# MusicGloves.net
KiCad netlist of a schematic drawn in EAGLE
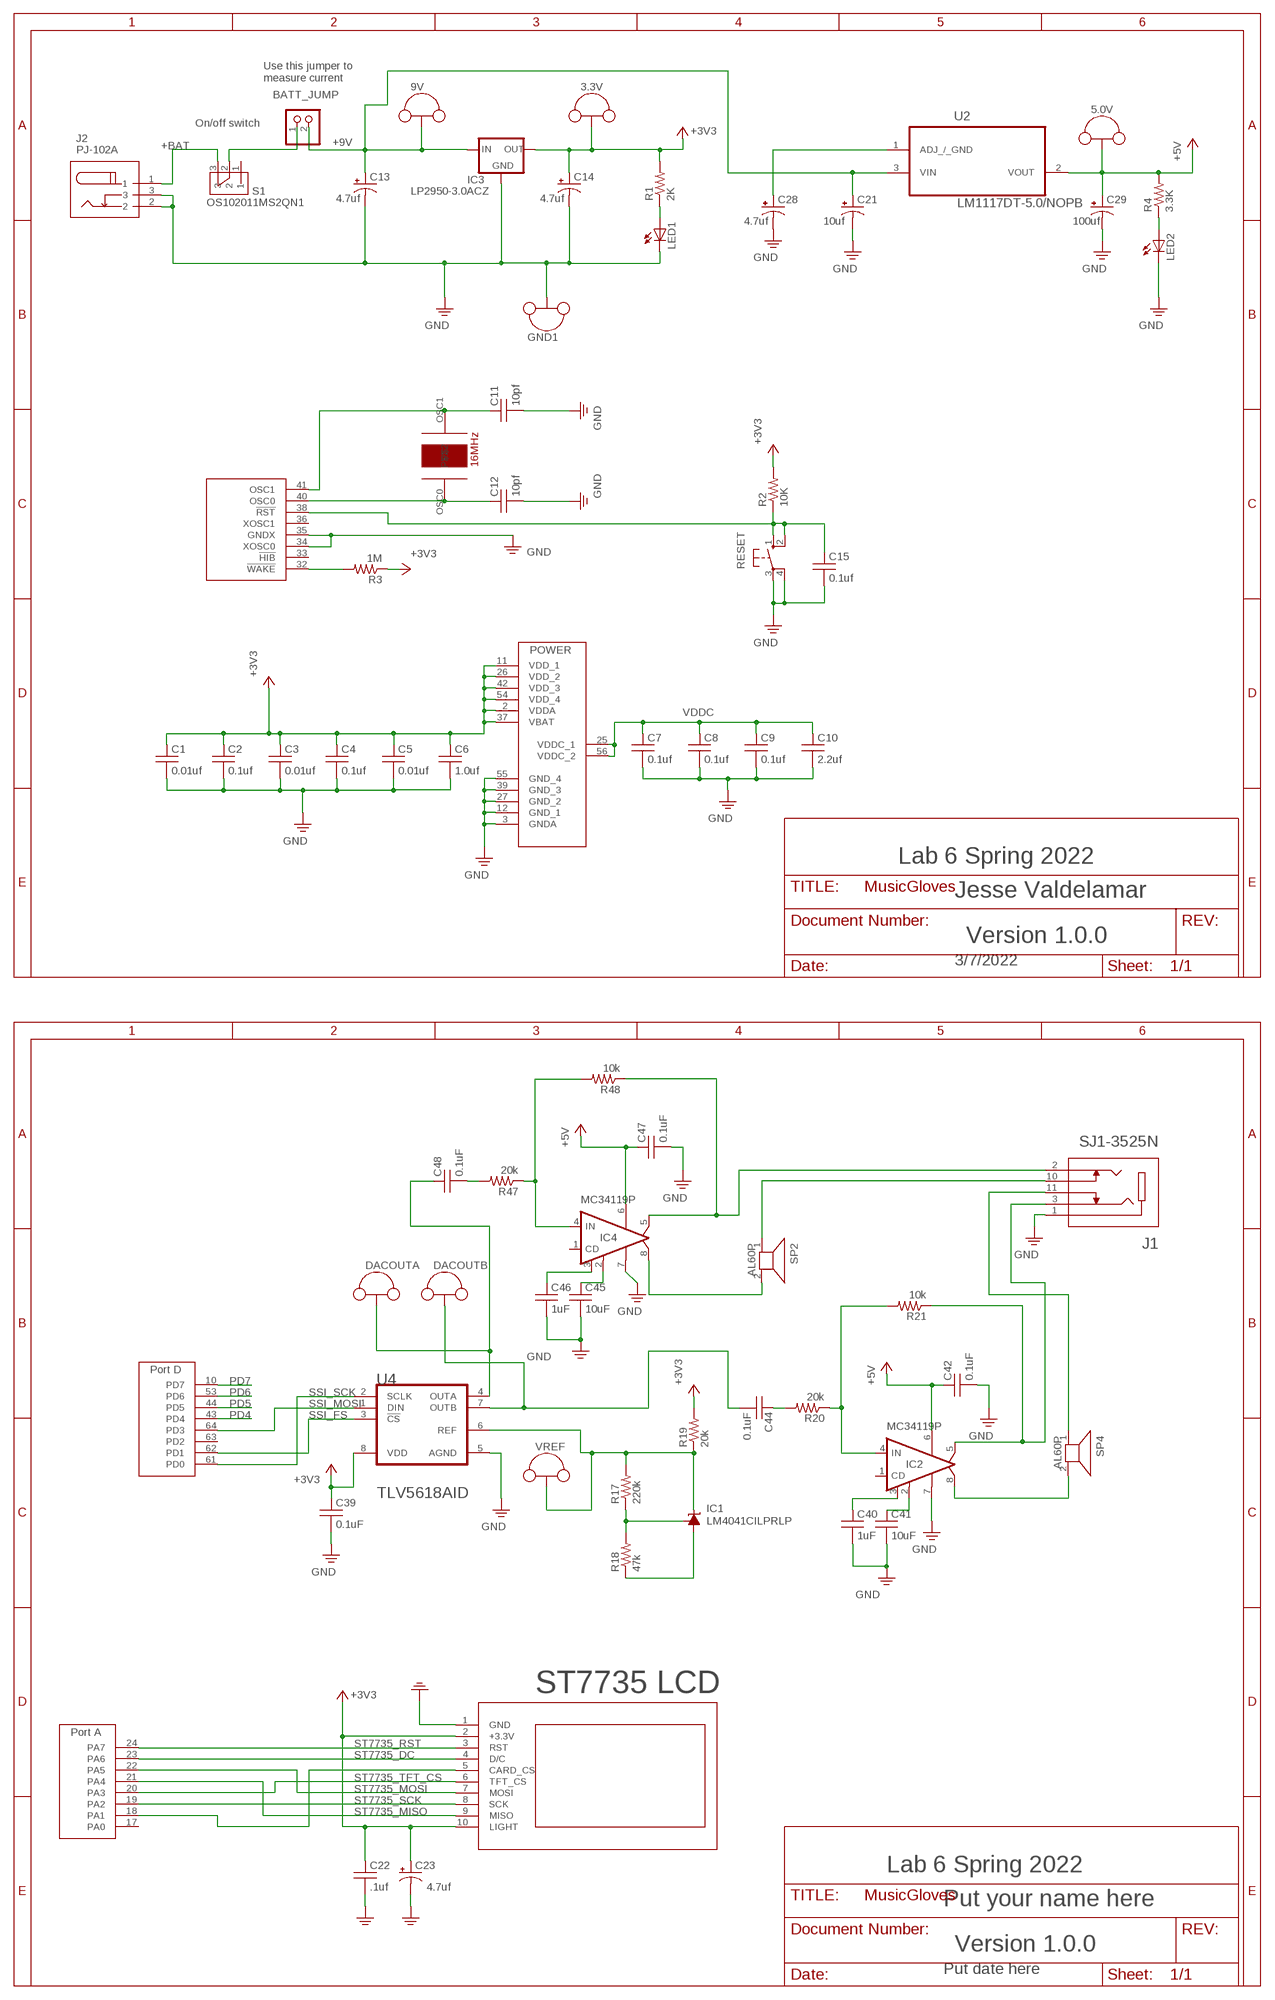
[diagram p0: schematic, sheet 1, part 1 of 2]
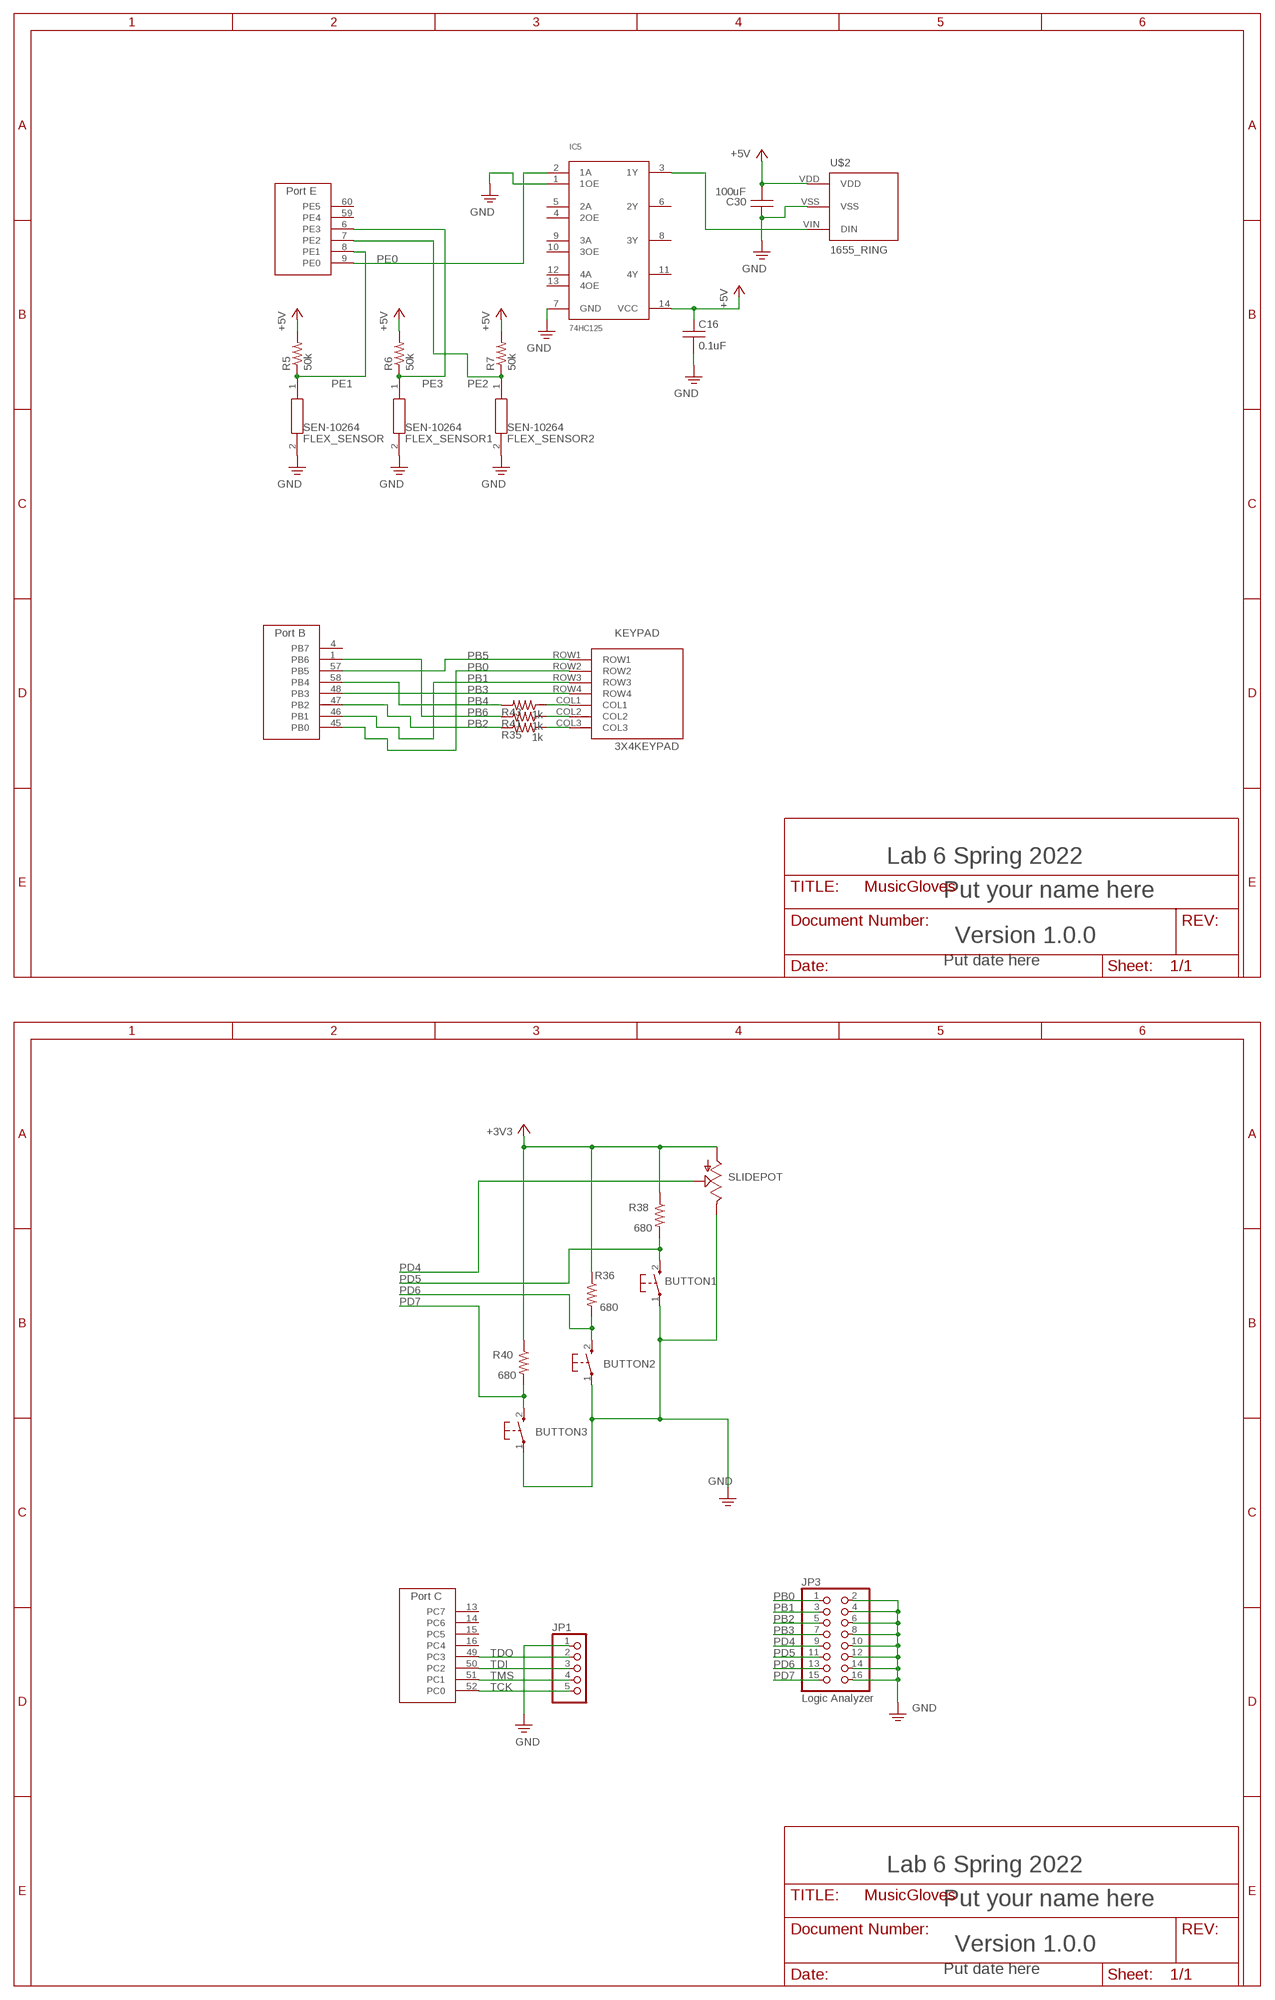
[diagram p1: schematic, sheet 1, part 2 of 2]

(export (version "E")
  (design (tool "Eeschema 10.0.6"))
  (components
    (comp (ref "3.3V")
      (value "TP_LOOP")
      (footprint "eagle-import:TP_LOOP")
      (libsource (lib "eagle-import") (part "TP_LOOP"))
    )
    (comp (ref "5.0V")
      (value "TP_LOOP")
      (footprint "eagle-import:TP_LOOP")
      (libsource (lib "eagle-import") (part "TP_LOOP"))
    )
    (comp (ref "9V")
      (value "TP_LOOP")
      (footprint "eagle-import:TP_LOOP")
      (libsource (lib "eagle-import") (part "TP_LOOP"))
    )
    (comp (ref "BATT_JUMP")
      (value "PINHD-1X2")
      (footprint "eagle-import:1X02")
      (libsource (lib "eagle-import") (part "PINHD-1X2"))
    )
    (comp (ref "BUTTON1")
      (value "B3F_1052_2HOLE")
      (footprint "eagle-import:B3F-10XX_2HOLE")
      (libsource (lib "eagle-import") (part "B3F_1052_2HOLE"))
    )
    (comp (ref "BUTTON2")
      (value "B3F_1052_2HOLE")
      (footprint "eagle-import:B3F-10XX_2HOLE")
      (libsource (lib "eagle-import") (part "B3F_1052_2HOLE"))
    )
    (comp (ref "BUTTON3")
      (value "B3F_1052_2HOLE")
      (footprint "eagle-import:B3F-10XX_2HOLE")
      (libsource (lib "eagle-import") (part "B3F_1052_2HOLE"))
    )
    (comp (ref "C1")
      (value "0.01uf")
      (footprint "eagle-import:CAP100MIL")
      (libsource (lib "eagle-import") (part "CAPACITOR025-024X044"))
    )
    (comp (ref "C2")
      (value "0.1uf")
      (footprint "eagle-import:CAP100MIL")
      (libsource (lib "eagle-import") (part "CAPACITOR025-024X044"))
    )
    (comp (ref "C3")
      (value "0.01uf")
      (footprint "eagle-import:CAP100MIL")
      (libsource (lib "eagle-import") (part "CAPACITOR025-024X044"))
    )
    (comp (ref "C4")
      (value "0.1uf")
      (footprint "eagle-import:CAP100MIL")
      (libsource (lib "eagle-import") (part "CAPACITOR025-024X044"))
    )
    (comp (ref "C5")
      (value "0.01uf")
      (footprint "eagle-import:CAP100MIL")
      (libsource (lib "eagle-import") (part "CAPACITOR025-024X044"))
    )
    (comp (ref "C6")
      (value "1.0uf")
      (footprint "eagle-import:CAP100MIL")
      (libsource (lib "eagle-import") (part "CAPACITOR025-024X044"))
    )
    (comp (ref "C7")
      (value "0.1uf")
      (footprint "eagle-import:CAP100MIL")
      (libsource (lib "eagle-import") (part "CAPACITOR025-024X044"))
    )
    (comp (ref "C8")
      (value "0.1uf")
      (footprint "eagle-import:CAP100MIL")
      (libsource (lib "eagle-import") (part "CAPACITOR025-024X044"))
    )
    (comp (ref "C9")
      (value "0.1uf")
      (footprint "eagle-import:CAP100MIL")
      (libsource (lib "eagle-import") (part "CAPACITOR025-024X044"))
    )
    (comp (ref "C10")
      (value "2.2uf")
      (footprint "eagle-import:CAP100MIL")
      (libsource (lib "eagle-import") (part "CAPACITOR025-024X044"))
    )
    (comp (ref "C11")
      (value "10pf")
      (footprint "eagle-import:CAP100MIL")
      (libsource (lib "eagle-import") (part "CAPACITOR025-024X044"))
    )
    (comp (ref "C12")
      (value "10pf")
      (footprint "eagle-import:CAP100MIL")
      (libsource (lib "eagle-import") (part "CAPACITOR025-024X044"))
    )
    (comp (ref "C13")
      (value "4.7uf")
      (footprint "eagle-import:CAP200MILPOLARIZED")
      (libsource (lib "eagle-import") (part "CAPACITOR_POLARIZEDE5-6"))
    )
    (comp (ref "C14")
      (value "4.7uf")
      (footprint "eagle-import:CAP200MILPOLARIZED")
      (libsource (lib "eagle-import") (part "CAPACITOR_POLARIZEDE5-6"))
    )
    (comp (ref "C15")
      (value "0.1uf")
      (footprint "eagle-import:CAP100MIL")
      (libsource (lib "eagle-import") (part "CAPACITOR025-024X044"))
    )
    (comp (ref "C16")
      (value "0.1uF")
      (footprint "eagle-import:CAP200MIL")
      (libsource (lib "eagle-import") (part "CAPACITOR050-024X044"))
    )
    (comp (ref "C21")
      (value "10uf")
      (footprint "eagle-import:CAP200MILPOLARIZED")
      (libsource (lib "eagle-import") (part "CAPACITOR_POLARIZEDE5-6"))
    )
    (comp (ref "C22")
      (value ".1uf")
      (footprint "eagle-import:CAP200MIL")
      (libsource (lib "eagle-import") (part "CAPACITOR050-024X044"))
    )
    (comp (ref "C23")
      (value "4.7uf")
      (footprint "eagle-import:CAP200MILPOLARIZED")
      (libsource (lib "eagle-import") (part "CAPACITOR_POLARIZEDE5-6"))
    )
    (comp (ref "C28")
      (value "4.7uf")
      (footprint "eagle-import:CAP200MILPOLARIZED")
      (libsource (lib "eagle-import") (part "CAPACITOR_POLARIZEDE5-6"))
    )
    (comp (ref "C29")
      (value "100uf")
      (footprint "eagle-import:CAP200MILPOLARIZED")
      (libsource (lib "eagle-import") (part "CAPACITOR_POLARIZEDE5-6"))
    )
    (comp (ref "C30")
      (value "100uF")
      (footprint "eagle-import:CAP200MIL")
      (libsource (lib "eagle-import") (part "CAPACITOR050-024X044"))
    )
    (comp (ref "C39")
      (value "0.1uF")
      (footprint "eagle-import:CAP200MIL")
      (libsource (lib "eagle-import") (part "CAPACITOR050-024X044"))
    )
    (comp (ref "C40")
      (value "1uF")
      (footprint "eagle-import:CAP200MIL")
      (libsource (lib "eagle-import") (part "CAPACITOR050-024X044"))
    )
    (comp (ref "C41")
      (value "10uF")
      (footprint "eagle-import:CAP200MIL")
      (libsource (lib "eagle-import") (part "CAPACITOR050-024X044"))
    )
    (comp (ref "C42")
      (value "0.1uF")
      (footprint "eagle-import:CAP200MIL")
      (libsource (lib "eagle-import") (part "CAPACITOR050-024X044"))
    )
    (comp (ref "C44")
      (value "0.1uF")
      (footprint "eagle-import:CAP200MIL")
      (libsource (lib "eagle-import") (part "CAPACITOR050-024X044"))
    )
    (comp (ref "C45")
      (value "10uF")
      (footprint "eagle-import:CAP200MIL")
      (libsource (lib "eagle-import") (part "CAPACITOR050-024X044"))
    )
    (comp (ref "C46")
      (value "1uF")
      (footprint "eagle-import:CAP200MIL")
      (libsource (lib "eagle-import") (part "CAPACITOR050-024X044"))
    )
    (comp (ref "C47")
      (value "0.1uF")
      (footprint "eagle-import:CAP200MIL")
      (libsource (lib "eagle-import") (part "CAPACITOR050-024X044"))
    )
    (comp (ref "C48")
      (value "0.1uF")
      (footprint "eagle-import:CAP200MIL")
      (libsource (lib "eagle-import") (part "CAPACITOR050-024X044"))
    )
    (comp (ref "DACOUTA")
      (value "TP_LOOP")
      (footprint "eagle-import:TP_LOOP")
      (libsource (lib "eagle-import") (part "TP_LOOP"))
    )
    (comp (ref "DACOUTB")
      (value "TP_LOOP")
      (footprint "eagle-import:TP_LOOP")
      (libsource (lib "eagle-import") (part "TP_LOOP"))
    )
    (comp (ref "FLEX_SENSOR")
      (value "SEN-10264")
      (footprint "eagle-import:RESAD2700W1900L700D500")
      (libsource (lib "eagle-import") (part "SEN-10264"))
    )
    (comp (ref "FLEX_SENSOR1")
      (value "SEN-10264")
      (footprint "eagle-import:RESAD2700W1900L700D500")
      (libsource (lib "eagle-import") (part "SEN-10264"))
    )
    (comp (ref "FLEX_SENSOR2")
      (value "SEN-10264")
      (footprint "eagle-import:RESAD2700W1900L700D500")
      (libsource (lib "eagle-import") (part "SEN-10264"))
    )
    (comp (ref "GND1")
      (value "TP_LOOP")
      (footprint "eagle-import:TP_LOOP")
      (libsource (lib "eagle-import") (part "TP_LOOP"))
    )
    (comp (ref "IC1")
      (value "LM4041CILPRLP")
      (footprint "eagle-import:LP_O-PBCY-W3")
      (fields
        (field (name "DIGI-KEY_PART_NUMBER") "296-22173-1-ND")
        (field (name "MF") "Texas Instruments")
        (field (name "MP") "LM4041CILPR")
      )
      (libsource (lib "eagle-import") (part "LM4041CILPRLP"))
    )
    (comp (ref "IC2")
      (value "MC34119P")
      (footprint "eagle-import:DIL08")
      (fields (field (name "MF") "NXP Semiconductors") (field (name "MP") "MC34119"))
      (libsource (lib "eagle-import") (part "MC34119P"))
    )
    (comp (ref "IC3")
      (value "LP2950-3.0ACZ")
      (footprint "eagle-import:TO92")
      (libsource (lib "eagle-import") (part "LP2950ACZ-3.0"))
    )
    (comp (ref "IC4")
      (value "MC34119P")
      (footprint "eagle-import:DIL08")
      (fields (field (name "MF") "NXP Semiconductors") (field (name "MP") "MC34119"))
      (libsource (lib "eagle-import") (part "MC34119P"))
    )
    (comp (ref "IC5")
      (value "74HC125")
      (footprint "eagle-import:SOIC-14")
      (fields (field (name "MF") "Nexperia USA"))
      (libsource (lib "eagle-import") (part "74HC125"))
    )
    (comp (ref "J1")
      (value "SJ1-3525N")
      (footprint "eagle-import:CUI_SJ1-3525N")
      (fields (field (name "MANUFACTURER") "CUI"))
      (libsource (lib "eagle-import") (part "SJ1-3525N"))
    )
    (comp (ref "J2")
      (value "PJ-102A")
      (footprint "eagle-import:PJ-102AH")
      (fields (field (name "MOUSER_PART_NUMBER") "490-PJ-102A"))
      (libsource (lib "eagle-import") (part "PJ-102A"))
    )
    (comp (ref "JP1")
      (value "PINHD-1X5")
      (footprint "eagle-import:1X05")
      (libsource (lib "eagle-import") (part "PINHD-1X5"))
    )
    (comp (ref "JP3")
      (value "Logic Analyzer")
      (footprint "eagle-import:2X08")
      (libsource (lib "eagle-import") (part "PINHD-2X8"))
    )
    (comp (ref "KEYPAD")
      (value "3X4KEYPAD")
      (footprint "eagle-import:3X4KEYPAD")
      (libsource (lib "eagle-import") (part "3X4KEYPAD"))
    )
    (comp (ref "LED1")
      (value "LED3MM")
      (footprint "eagle-import:LED3MM")
      (libsource (lib "eagle-import") (part "LED3MM"))
    )
    (comp (ref "LED2")
      (value "LED3MM")
      (footprint "eagle-import:LED3MM")
      (libsource (lib "eagle-import") (part "LED3MM"))
    )
    (comp (ref "R1")
      (value "2K")
      (footprint "eagle-import:RES200MIL")
      (libsource (lib "eagle-import") (part "RESISTOR0204/5"))
    )
    (comp (ref "R2")
      (value "10K")
      (footprint "eagle-import:RES200MIL")
      (libsource (lib "eagle-import") (part "RESISTOR0204/5"))
    )
    (comp (ref "R3")
      (value "1M")
      (footprint "eagle-import:RES200MIL")
      (libsource (lib "eagle-import") (part "RESISTOR0204/5"))
    )
    (comp (ref "R4")
      (value "3.3K")
      (footprint "eagle-import:RES200MIL")
      (libsource (lib "eagle-import") (part "RESISTOR0204/5"))
    )
    (comp (ref "R5")
      (value "50k")
      (footprint "eagle-import:RES200MIL")
      (libsource (lib "eagle-import") (part "RESISTOR0204/5"))
    )
    (comp (ref "R6")
      (value "50k")
      (footprint "eagle-import:RES200MIL")
      (libsource (lib "eagle-import") (part "RESISTOR0204/5"))
    )
    (comp (ref "R7")
      (value "50k")
      (footprint "eagle-import:RES200MIL")
      (libsource (lib "eagle-import") (part "RESISTOR0204/5"))
    )
    (comp (ref "R17")
      (value "220k")
      (footprint "eagle-import:RES200MIL")
      (libsource (lib "eagle-import") (part "RESISTOR0204/5"))
    )
    (comp (ref "R18")
      (value "47k")
      (footprint "eagle-import:RES200MIL")
      (libsource (lib "eagle-import") (part "RESISTOR0204/5"))
    )
    (comp (ref "R19")
      (value "20k")
      (footprint "eagle-import:RES200MIL")
      (libsource (lib "eagle-import") (part "RESISTOR0204/5"))
    )
    (comp (ref "R20")
      (value "20k")
      (footprint "eagle-import:RES200MIL")
      (libsource (lib "eagle-import") (part "RESISTOR0204/5"))
    )
    (comp (ref "R21")
      (value "10k")
      (footprint "eagle-import:RES200MIL")
      (libsource (lib "eagle-import") (part "RESISTOR0204/5"))
    )
    (comp (ref "R35")
      (value "1k")
      (footprint "eagle-import:0204_5")
      (libsource (lib "eagle-import") (part "R-US_0204/5"))
    )
    (comp (ref "R36")
      (value "680")
      (footprint "eagle-import:0204_5")
      (libsource (lib "eagle-import") (part "R-US_0204/5"))
    )
    (comp (ref "R38")
      (value "680")
      (footprint "eagle-import:0204_5")
      (libsource (lib "eagle-import") (part "R-US_0204/5"))
    )
    (comp (ref "R40")
      (value "680")
      (footprint "eagle-import:0204_5")
      (libsource (lib "eagle-import") (part "R-US_0204/5"))
    )
    (comp (ref "R41")
      (value "1k")
      (footprint "eagle-import:0204_5")
      (libsource (lib "eagle-import") (part "R-US_0204/5"))
    )
    (comp (ref "R43")
      (value "1k")
      (footprint "eagle-import:0204_5")
      (libsource (lib "eagle-import") (part "R-US_0204/5"))
    )
    (comp (ref "R47")
      (value "20k")
      (footprint "eagle-import:RES200MIL")
      (libsource (lib "eagle-import") (part "RESISTOR0204/5"))
    )
    (comp (ref "R48")
      (value "10k")
      (footprint "eagle-import:RES200MIL")
      (libsource (lib "eagle-import") (part "RESISTOR0204/5"))
    )
    (comp (ref "RESET")
      (value "B3F-1052")
      (footprint "eagle-import:B3F-10XX")
      (fields (field (name "MPN") "B3F-1000"))
      (libsource (lib "eagle-import") (part "B3F-1052"))
    )
    (comp (ref "S1")
      (value "OS102011MS2QN1")
      (footprint "eagle-import:SW_OS102011MS2QN1")
      (fields (field (name "MF") "C&K"))
      (libsource (lib "eagle-import") (part "OS102011MS2QN1"))
    )
    (comp (ref "SLIDEPOT")
      (value "POTENTIOMETER_PTA2043B25U")
      (footprint "eagle-import:PTA2043")
      (libsource (lib "eagle-import") (part "POTENTIOMETER_PTA2043B25U"))
    )
    (comp (ref "SP2")
      (value "AL60P")
      (footprint "eagle-import:AL60P")
      (libsource (lib "eagle-import") (part "AL60P"))
    )
    (comp (ref "SP4")
      (value "AL60P")
      (footprint "eagle-import:AL60P")
      (libsource (lib "eagle-import") (part "AL60P"))
    )
    (comp (ref "U$2")
      (value "1655_RING")
      (footprint "eagle-import:LED_1655_RING")
      (libsource (lib "eagle-import") (part "1655_RING"))
    )
    (comp (ref "U$3")
      (value "ST7735")
      (footprint "eagle-import:ST7735")
      (libsource (lib "eagle-import") (part "ST7735"))
    )
    (comp (ref "U1")
      (value "TM4C123GH6PM")
      (footprint "eagle-import:QFP50P1200X1200X160-64N")
      (libsource (lib "eagle-import") (part "TM4C123GH6PM"))
    )
    (comp (ref "U2")
      (value "LM1117DT-5.0/NOPB")
      (footprint "eagle-import:TO228P970X238-3N")
      (fields (field (name "MF") "Texas Instruments"))
      (libsource (lib "eagle-import") (part "LM1117DT-5.0/NOPB"))
    )
    (comp (ref "U4")
      (value "TEXAS_INSTRUMENTS_TLV5618AIDTEXAS_INSTRUMENTS_TLV5618AID_0_0")
      (footprint "eagle-import:TEXAS_INSTRUMENTS_TLV5618AID_0")
      (fields (field (name "MF") "Texas Instruments") (field (name "MPN") "TLV5618AID"))
      (libsource (lib "eagle-import") (part "TEXAS_INSTRUMENTS_TLV5618AIDTEXAS_INSTRUMENTS_TLV5618AID_0_0"))
    )
    (comp (ref "VREF")
      (value "TP_LOOP")
      (footprint "eagle-import:TP_LOOP")
      (libsource (lib "eagle-import") (part "TP_LOOP"))
    )
    (comp (ref "Y1")
      (value "16MHZ_CRYSTAL")
      (footprint "eagle-import:16MHZ_CRYSTAL")
      (libsource (lib "eagle-import") (part "16MHZ_CRYSTAL"))
    )
  )
  (nets
    (net (code "1") (name "+3V3") (class "Default")
      (node (ref "3.3V") (pin "P$1") (pinfunction "TP_P$1") (pintype "bidirectional"))
      (node (ref "3.3V") (pin "P$2") (pinfunction "TP_P$2") (pintype "bidirectional"))
      (node (ref "C1") (pin "1") (pinfunction "1_1") (pintype "passive"))
      (node (ref "C14") (pin "+") (pinfunction "+_+") (pintype "passive"))
      (node (ref "C2") (pin "1") (pinfunction "1_1") (pintype "passive"))
      (node (ref "C22") (pin "1") (pinfunction "1_1") (pintype "passive"))
      (node (ref "C23") (pin "+") (pinfunction "+_+") (pintype "passive"))
      (node (ref "C3") (pin "1") (pinfunction "1_1") (pintype "passive"))
      (node (ref "C39") (pin "1") (pinfunction "1_1") (pintype "passive"))
      (node (ref "C4") (pin "1") (pinfunction "1_1") (pintype "passive"))
      (node (ref "C5") (pin "1") (pinfunction "1_1") (pintype "passive"))
      (node (ref "C6") (pin "1") (pinfunction "1_1") (pintype "passive"))
      (node (ref "IC3") (pin "1") (pinfunction "OUT_1") (pintype "passive"))
      (node (ref "R1") (pin "2") (pinfunction "2_2") (pintype "passive"))
      (node (ref "R19") (pin "2") (pinfunction "2_2") (pintype "passive"))
      (node (ref "R2") (pin "2") (pinfunction "2_2") (pintype "passive"))
      (node (ref "R3") (pin "1") (pinfunction "1_1") (pintype "passive"))
      (node (ref "R36") (pin "1") (pinfunction "1_1") (pintype "passive"))
      (node (ref "R38") (pin "1") (pinfunction "1_1") (pintype "passive"))
      (node (ref "R40") (pin "1") (pinfunction "1_1") (pintype "passive"))
      (node (ref "SLIDEPOT") (pin "3") (pinfunction "A_3") (pintype "passive"))
      (node (ref "U$3") (pin "10") (pinfunction "LIGHT_10") (pintype "bidirectional"))
      (node (ref "U$3") (pin "2") (pinfunction "+3.3V_2") (pintype "bidirectional"))
      (node (ref "U1") (pin "11") (pinfunction "VDD_1_11") (pintype "bidirectional"))
      (node (ref "U1") (pin "2") (pinfunction "VDDA_2") (pintype "bidirectional"))
      (node (ref "U1") (pin "26") (pinfunction "VDD_2_26") (pintype "bidirectional"))
      (node (ref "U1") (pin "37") (pinfunction "VBAT_37") (pintype "bidirectional"))
      (node (ref "U1") (pin "42") (pinfunction "VDD_3_42") (pintype "bidirectional"))
      (node (ref "U1") (pin "54") (pinfunction "VDD_4_54") (pintype "bidirectional"))
      (node (ref "U4") (pin "8") (pinfunction "VDD_8") (pintype "power_in"))
    )
    (net (code "2") (name "+5V") (class "Default")
      (node (ref "5.0V") (pin "P$1") (pinfunction "TP_P$1") (pintype "bidirectional"))
      (node (ref "5.0V") (pin "P$2") (pinfunction "TP_P$2") (pintype "bidirectional"))
      (node (ref "C16") (pin "1") (pinfunction "1_1") (pintype "passive"))
      (node (ref "C29") (pin "+") (pinfunction "+_+") (pintype "passive"))
      (node (ref "C30") (pin "2") (pinfunction "2_2") (pintype "passive"))
      (node (ref "C42") (pin "1") (pinfunction "1_1") (pintype "passive"))
      (node (ref "C47") (pin "1") (pinfunction "1_1") (pintype "passive"))
      (node (ref "IC2") (pin "6") (pinfunction "VCC_6") (pintype "power_in"))
      (node (ref "IC4") (pin "6") (pinfunction "VCC_6") (pintype "power_in"))
      (node (ref "IC5") (pin "14") (pinfunction "VCC_14") (pintype "bidirectional"))
      (node (ref "R4") (pin "2") (pinfunction "2_2") (pintype "passive"))
      (node (ref "R5") (pin "2") (pinfunction "2_2") (pintype "passive"))
      (node (ref "R6") (pin "2") (pinfunction "2_2") (pintype "passive"))
      (node (ref "R7") (pin "2") (pinfunction "2_2") (pintype "passive"))
      (node (ref "U$2") (pin "VDD") (pinfunction "VDD_VDD") (pintype "power_in"))
      (node (ref "U2") (pin "2") (pinfunction "VOUT_2") (pintype "output"))
    )
    (net (code "3") (name "/+9V") (class "Default")
      (node (ref "9V") (pin "P$1") (pinfunction "TP_P$1") (pintype "bidirectional"))
      (node (ref "9V") (pin "P$2") (pinfunction "TP_P$2") (pintype "bidirectional"))
      (node (ref "BATT_JUMP") (pin "2") (pinfunction "2_2") (pintype "passive"))
      (node (ref "C13") (pin "+") (pinfunction "+_+") (pintype "passive"))
      (node (ref "C21") (pin "+") (pinfunction "+_+") (pintype "passive"))
      (node (ref "IC3") (pin "3") (pinfunction "IN_3") (pintype "input"))
      (node (ref "U2") (pin "3") (pinfunction "VIN_3") (pintype "input"))
    )
    (net (code "4") (name "/+BAT") (class "Default")
      (node (ref "J2") (pin "1") (pinfunction "1_1") (pintype "bidirectional"))
      (node (ref "S1") (pin "3") (pinfunction "3_3") (pintype "passive"))
    )
    (net (code "5") (name "/PB0") (class "Default")
      (node (ref "JP3") (pin "1") (pinfunction "1_1") (pintype "passive"))
      (node (ref "KEYPAD") (pin "ROW2") (pinfunction "ROW2_ROW2") (pintype "bidirectional"))
      (node (ref "U1") (pin "45") (pinfunction "PB0_45") (pintype "bidirectional"))
    )
    (net (code "6") (name "/PB1") (class "Default")
      (node (ref "JP3") (pin "3") (pinfunction "3_3") (pintype "passive"))
      (node (ref "KEYPAD") (pin "ROW3") (pinfunction "ROW3_ROW3") (pintype "bidirectional"))
      (node (ref "U1") (pin "46") (pinfunction "PB1_46") (pintype "bidirectional"))
    )
    (net (code "7") (name "/PB2") (class "Default")
      (node (ref "JP3") (pin "5") (pinfunction "5_5") (pintype "passive"))
      (node (ref "R35") (pin "2") (pinfunction "2_2") (pintype "passive"))
      (node (ref "U1") (pin "47") (pinfunction "PB2_47") (pintype "bidirectional"))
    )
    (net (code "8") (name "/PB3") (class "Default")
      (node (ref "JP3") (pin "7") (pinfunction "7_7") (pintype "passive"))
      (node (ref "KEYPAD") (pin "ROW4") (pinfunction "ROW4_ROW4") (pintype "bidirectional"))
      (node (ref "U1") (pin "48") (pinfunction "PB3_48") (pintype "bidirectional"))
    )
    (net (code "9") (name "/PB4") (class "Default")
      (node (ref "R43") (pin "2") (pinfunction "2_2") (pintype "passive"))
      (node (ref "U1") (pin "58") (pinfunction "PB4_58") (pintype "bidirectional"))
    )
    (net (code "10") (name "/PB5") (class "Default")
      (node (ref "KEYPAD") (pin "ROW1") (pinfunction "ROW1_ROW1") (pintype "bidirectional"))
      (node (ref "U1") (pin "57") (pinfunction "PB5_57") (pintype "bidirectional"))
    )
    (net (code "11") (name "/PB6") (class "Default")
      (node (ref "R41") (pin "2") (pinfunction "2_2") (pintype "passive"))
      (node (ref "U1") (pin "1") (pinfunction "PB6_1") (pintype "bidirectional"))
    )
    (net (code "12") (name "/PD4") (class "Default")
      (node (ref "JP3") (pin "9") (pinfunction "9_9") (pintype "passive"))
      (node (ref "SLIDEPOT") (pin "2") (pinfunction "S_2") (pintype "passive"))
      (node (ref "U1") (pin "43") (pinfunction "PD4_43") (pintype "bidirectional"))
    )
    (net (code "13") (name "/PD5") (class "Default")
      (node (ref "BUTTON1") (pin "2") (pinfunction "S_2") (pintype "passive"))
      (node (ref "JP3") (pin "11") (pinfunction "11_11") (pintype "passive"))
      (node (ref "R38") (pin "2") (pinfunction "2_2") (pintype "passive"))
      (node (ref "U1") (pin "44") (pinfunction "PD5_44") (pintype "bidirectional"))
    )
    (net (code "14") (name "/PD6") (class "Default")
      (node (ref "BUTTON2") (pin "2") (pinfunction "S_2") (pintype "passive"))
      (node (ref "JP3") (pin "13") (pinfunction "13_13") (pintype "passive"))
      (node (ref "R36") (pin "2") (pinfunction "2_2") (pintype "passive"))
      (node (ref "U1") (pin "53") (pinfunction "PD6_53") (pintype "bidirectional"))
    )
    (net (code "15") (name "/PD7") (class "Default")
      (node (ref "BUTTON3") (pin "2") (pinfunction "S_2") (pintype "passive"))
      (node (ref "JP3") (pin "15") (pinfunction "15_15") (pintype "passive"))
      (node (ref "R40") (pin "2") (pinfunction "2_2") (pintype "passive"))
      (node (ref "U1") (pin "10") (pinfunction "PD7_10") (pintype "bidirectional"))
    )
    (net (code "16") (name "/PE0") (class "Default")
      (node (ref "IC5") (pin "2") (pinfunction "1A_2") (pintype "bidirectional"))
      (node (ref "U1") (pin "9") (pinfunction "PE0_9") (pintype "bidirectional"))
    )
    (net (code "17") (name "/PE1") (class "Default")
      (node (ref "FLEX_SENSOR") (pin "1") (pinfunction "1_1") (pintype "bidirectional"))
      (node (ref "R5") (pin "1") (pinfunction "1_1") (pintype "passive"))
      (node (ref "U1") (pin "8") (pinfunction "PE1_8") (pintype "bidirectional"))
    )
    (net (code "18") (name "/PE2") (class "Default")
      (node (ref "FLEX_SENSOR2") (pin "1") (pinfunction "1_1") (pintype "bidirectional"))
      (node (ref "R7") (pin "1") (pinfunction "1_1") (pintype "passive"))
      (node (ref "U1") (pin "7") (pinfunction "PE2_7") (pintype "bidirectional"))
    )
    (net (code "19") (name "/PE3") (class "Default")
      (node (ref "FLEX_SENSOR1") (pin "1") (pinfunction "1_1") (pintype "bidirectional"))
      (node (ref "R6") (pin "1") (pinfunction "1_1") (pintype "passive"))
      (node (ref "U1") (pin "6") (pinfunction "PE3_6") (pintype "bidirectional"))
    )
    (net (code "20") (name "/SSI_FS") (class "Default")
      (node (ref "U1") (pin "62") (pinfunction "PD1_62") (pintype "bidirectional"))
      (node (ref "U4") (pin "3") (pinfunction "~{CS}_3") (pintype "input"))
    )
    (net (code "21") (name "/SSI_MOSI") (class "Default")
      (node (ref "U1") (pin "64") (pinfunction "PD3_64") (pintype "bidirectional"))
      (node (ref "U4") (pin "1") (pinfunction "DIN_1") (pintype "input"))
    )
    (net (code "22") (name "/SSI_SCK") (class "Default")
      (node (ref "U1") (pin "61") (pinfunction "PD0_61") (pintype "bidirectional"))
      (node (ref "U4") (pin "2") (pinfunction "SCLK_2") (pintype "input"))
    )
    (net (code "23") (name "/ST7735_DC") (class "Default")
      (node (ref "U$3") (pin "4") (pinfunction "D/C_4") (pintype "bidirectional"))
      (node (ref "U1") (pin "23") (pinfunction "PA6_23") (pintype "bidirectional"))
    )
    (net (code "24") (name "/ST7735_MISO") (class "Default")
      (node (ref "U$3") (pin "9") (pinfunction "MISO_9") (pintype "bidirectional"))
      (node (ref "U1") (pin "21") (pinfunction "PA4_21") (pintype "bidirectional"))
    )
    (net (code "25") (name "/ST7735_MOSI") (class "Default")
      (node (ref "U$3") (pin "7") (pinfunction "MOSI_7") (pintype "bidirectional"))
      (node (ref "U1") (pin "22") (pinfunction "PA5_22") (pintype "bidirectional"))
    )
    (net (code "26") (name "/ST7735_RST") (class "Default")
      (node (ref "U$3") (pin "3") (pinfunction "RST_3") (pintype "bidirectional"))
      (node (ref "U1") (pin "24") (pinfunction "PA7_24") (pintype "bidirectional"))
    )
    (net (code "27") (name "/ST7735_SCK") (class "Default")
      (node (ref "U$3") (pin "8") (pinfunction "SCK_8") (pintype "bidirectional"))
      (node (ref "U1") (pin "19") (pinfunction "PA2_19") (pintype "bidirectional"))
    )
    (net (code "28") (name "/ST7735_TFT_CS") (class "Default")
      (node (ref "U$3") (pin "6") (pinfunction "TFT_CS_6") (pintype "bidirectional"))
      (node (ref "U1") (pin "20") (pinfunction "PA3_20") (pintype "bidirectional"))
    )
    (net (code "29") (name "/TCK") (class "Default")
      (node (ref "JP1") (pin "5") (pinfunction "5_5") (pintype "passive"))
      (node (ref "U1") (pin "52") (pinfunction "PC0_52") (pintype "bidirectional"))
    )
    (net (code "30") (name "/TDI") (class "Default")
      (node (ref "JP1") (pin "3") (pinfunction "3_3") (pintype "passive"))
      (node (ref "U1") (pin "50") (pinfunction "PC2_50") (pintype "bidirectional"))
    )
    (net (code "31") (name "/TDO") (class "Default")
      (node (ref "JP1") (pin "2") (pinfunction "2_2") (pintype "passive"))
      (node (ref "U1") (pin "49") (pinfunction "PC3_49") (pintype "bidirectional"))
    )
    (net (code "32") (name "/TMS") (class "Default")
      (node (ref "JP1") (pin "4") (pinfunction "4_4") (pintype "passive"))
      (node (ref "U1") (pin "51") (pinfunction "PC1_51") (pintype "bidirectional"))
    )
    (net (code "33") (name "/VDDC") (class "Default")
      (node (ref "C10") (pin "1") (pinfunction "1_1") (pintype "passive"))
      (node (ref "C7") (pin "1") (pinfunction "1_1") (pintype "passive"))
      (node (ref "C8") (pin "1") (pinfunction "1_1") (pintype "passive"))
      (node (ref "C9") (pin "1") (pinfunction "1_1") (pintype "passive"))
      (node (ref "U1") (pin "25") (pinfunction "VDDC_1_25") (pintype "bidirectional"))
      (node (ref "U1") (pin "56") (pinfunction "VDDC_2_56") (pintype "bidirectional"))
    )
    (net (code "34") (name "GND") (class "Default")
      (node (ref "BUTTON1") (pin "1") (pinfunction "P_1") (pintype "passive"))
      (node (ref "BUTTON2") (pin "1") (pinfunction "P_1") (pintype "passive"))
      (node (ref "BUTTON3") (pin "1") (pinfunction "P_1") (pintype "passive"))
      (node (ref "C1") (pin "2") (pinfunction "2_2") (pintype "passive"))
      (node (ref "C10") (pin "2") (pinfunction "2_2") (pintype "passive"))
      (node (ref "C11") (pin "2") (pinfunction "2_2") (pintype "passive"))
      (node (ref "C12") (pin "2") (pinfunction "2_2") (pintype "passive"))
      (node (ref "C13") (pin "-") (pinfunction "-_-") (pintype "passive"))
      (node (ref "C14") (pin "-") (pinfunction "-_-") (pintype "passive"))
      (node (ref "C15") (pin "2") (pinfunction "2_2") (pintype "passive"))
      (node (ref "C16") (pin "2") (pinfunction "2_2") (pintype "passive"))
      (node (ref "C2") (pin "2") (pinfunction "2_2") (pintype "passive"))
      (node (ref "C21") (pin "-") (pinfunction "-_-") (pintype "passive"))
      (node (ref "C22") (pin "2") (pinfunction "2_2") (pintype "passive"))
      (node (ref "C23") (pin "-") (pinfunction "-_-") (pintype "passive"))
      (node (ref "C28") (pin "-") (pinfunction "-_-") (pintype "passive"))
      (node (ref "C29") (pin "-") (pinfunction "-_-") (pintype "passive"))
      (node (ref "C3") (pin "2") (pinfunction "2_2") (pintype "passive"))
      (node (ref "C30") (pin "1") (pinfunction "1_1") (pintype "passive"))
      (node (ref "C39") (pin "2") (pinfunction "2_2") (pintype "passive"))
      (node (ref "C4") (pin "2") (pinfunction "2_2") (pintype "passive"))
      (node (ref "C40") (pin "2") (pinfunction "2_2") (pintype "passive"))
      (node (ref "C41") (pin "2") (pinfunction "2_2") (pintype "passive"))
      (node (ref "C42") (pin "2") (pinfunction "2_2") (pintype "passive"))
      (node (ref "C45") (pin "2") (pinfunction "2_2") (pintype "passive"))
      (node (ref "C46") (pin "2") (pinfunction "2_2") (pintype "passive"))
      (node (ref "C47") (pin "2") (pinfunction "2_2") (pintype "passive"))
      (node (ref "C5") (pin "2") (pinfunction "2_2") (pintype "passive"))
      (node (ref "C6") (pin "2") (pinfunction "2_2") (pintype "passive"))
      (node (ref "C7") (pin "2") (pinfunction "2_2") (pintype "passive"))
      (node (ref "C8") (pin "2") (pinfunction "2_2") (pintype "passive"))
      (node (ref "C9") (pin "2") (pinfunction "2_2") (pintype "passive"))
      (node (ref "FLEX_SENSOR") (pin "2") (pinfunction "2_2") (pintype "bidirectional"))
      (node (ref "FLEX_SENSOR1") (pin "2") (pinfunction "2_2") (pintype "bidirectional"))
      (node (ref "FLEX_SENSOR2") (pin "2") (pinfunction "2_2") (pintype "bidirectional"))
      (node (ref "GND1") (pin "P$1") (pinfunction "TP_P$1") (pintype "bidirectional"))
      (node (ref "GND1") (pin "P$2") (pinfunction "TP_P$2") (pintype "bidirectional"))
      (node (ref "IC2") (pin "7") (pinfunction "GND_7") (pintype "power_in"))
      (node (ref "IC3") (pin "2") (pinfunction "GND_2") (pintype "input"))
      (node (ref "IC4") (pin "7") (pinfunction "GND_7") (pintype "power_in"))
      (node (ref "IC5") (pin "1") (pinfunction "1OE_1") (pintype "bidirectional"))
      (node (ref "IC5") (pin "7") (pinfunction "GND_7") (pintype "bidirectional"))
      (node (ref "J1") (pin "1") (pinfunction "1_1") (pintype "passive"))
      (node (ref "J2") (pin "2") (pinfunction "2_2") (pintype "bidirectional"))
      (node (ref "J2") (pin "3") (pinfunction "3_3") (pintype "bidirectional"))
      (node (ref "JP1") (pin "1") (pinfunction "1_1") (pintype "passive"))
      (node (ref "JP3") (pin "10") (pinfunction "10_10") (pintype "passive"))
      (node (ref "JP3") (pin "12") (pinfunction "12_12") (pintype "passive"))
      (node (ref "JP3") (pin "14") (pinfunction "14_14") (pintype "passive"))
      (node (ref "JP3") (pin "16") (pinfunction "16_16") (pintype "passive"))
      (node (ref "JP3") (pin "2") (pinfunction "2_2") (pintype "passive"))
      (node (ref "JP3") (pin "4") (pinfunction "4_4") (pintype "passive"))
      (node (ref "JP3") (pin "6") (pinfunction "6_6") (pintype "passive"))
      (node (ref "JP3") (pin "8") (pinfunction "8_8") (pintype "passive"))
      (node (ref "LED1") (pin "K") (pinfunction "C_K") (pintype "passive"))
      (node (ref "LED2") (pin "K") (pinfunction "C_K") (pintype "passive"))
      (node (ref "RESET") (pin "3") (pinfunction "P_3") (pintype "passive"))
      (node (ref "RESET") (pin "4") (pinfunction "P1_4") (pintype "passive"))
      (node (ref "SLIDEPOT") (pin "1") (pinfunction "E_1") (pintype "passive"))
      (node (ref "U$2") (pin "VSS") (pinfunction "VSS_VSS") (pintype "power_in"))
      (node (ref "U$3") (pin "1") (pinfunction "GND_1") (pintype "bidirectional"))
      (node (ref "U1") (pin "12") (pinfunction "GND_1_12") (pintype "bidirectional"))
      (node (ref "U1") (pin "27") (pinfunction "GND_2_27") (pintype "bidirectional"))
      (node (ref "U1") (pin "3") (pinfunction "GNDA_3") (pintype "bidirectional"))
      (node (ref "U1") (pin "34") (pinfunction "XOSC0_34") (pintype "bidirectional"))
      (node (ref "U1") (pin "35") (pinfunction "GNDX_35") (pintype "bidirectional"))
      (node (ref "U1") (pin "39") (pinfunction "GND_3_39") (pintype "bidirectional"))
      (node (ref "U1") (pin "55") (pinfunction "GND_4_55") (pintype "bidirectional"))
      (node (ref "U4") (pin "5") (pinfunction "AGND_5") (pintype "power_in"))
    )
    (net (code "35") (name "Net-(BATT_JUMP-Pad1)") (class "Default")
      (node (ref "BATT_JUMP") (pin "1") (pinfunction "1_1") (pintype "passive"))
      (node (ref "S1") (pin "2") (pinfunction "2_2") (pintype "passive"))
    )
    (net (code "36") (name "Net-(C44-Pad1)") (class "Default")
      (node (ref "C44") (pin "1") (pinfunction "1_1") (pintype "passive"))
      (node (ref "R20") (pin "2") (pinfunction "2_2") (pintype "passive"))
    )
    (net (code "37") (name "Net-(C48-Pad2)") (class "Default")
      (node (ref "C48") (pin "2") (pinfunction "2_2") (pintype "passive"))
      (node (ref "R47") (pin "2") (pinfunction "2_2") (pintype "passive"))
    )
    (net (code "38") (name "Net-(IC1-A)") (class "Default")
      (node (ref "IC1") (pin "3") (pinfunction "A_3") (pintype "passive"))
      (node (ref "R18") (pin "1") (pinfunction "1_1") (pintype "passive"))
    )
    (net (code "39") (name "Net-(IC1-C)") (class "Default")
      (node (ref "IC1") (pin "2") (pinfunction "C_2") (pintype "passive"))
      (node (ref "R17") (pin "2") (pinfunction "2_2") (pintype "passive"))
      (node (ref "R19") (pin "1") (pinfunction "1_1") (pintype "passive"))
      (node (ref "U4") (pin "6") (pinfunction "REF_6") (pintype "input"))
      (node (ref "VREF") (pin "P$1") (pinfunction "TP_P$1") (pintype "bidirectional"))
      (node (ref "VREF") (pin "P$2") (pinfunction "TP_P$2") (pintype "bidirectional"))
    )
    (net (code "40") (name "Net-(IC1-FB)") (class "Default")
      (node (ref "IC1") (pin "1") (pinfunction "FB_1") (pintype "passive"))
      (node (ref "R17") (pin "1") (pinfunction "1_1") (pintype "passive"))
      (node (ref "R18") (pin "2") (pinfunction "2_2") (pintype "passive"))
    )
    (net (code "41") (name "Net-(IC2-FC1)") (class "Default")
      (node (ref "C40") (pin "1") (pinfunction "1_1") (pintype "passive"))
      (node (ref "IC2") (pin "3") (pinfunction "FC1_3") (pintype "passive"))
    )
    (net (code "42") (name "Net-(IC2-FC2)") (class "Default")
      (node (ref "C41") (pin "1") (pinfunction "1_1") (pintype "passive"))
      (node (ref "IC2") (pin "2") (pinfunction "FC2_2") (pintype "passive"))
    )
    (net (code "43") (name "Net-(IC2-IN)") (class "Default")
      (node (ref "IC2") (pin "4") (pinfunction "IN_4") (pintype "input"))
      (node (ref "R20") (pin "1") (pinfunction "1_1") (pintype "passive"))
      (node (ref "R21") (pin "2") (pinfunction "2_2") (pintype "passive"))
    )
    (net (code "44") (name "Net-(IC2-VO1)") (class "Default")
      (node (ref "IC2") (pin "5") (pinfunction "VO1_5") (pintype "output"))
      (node (ref "J1") (pin "3") (pinfunction "3_3") (pintype "passive"))
      (node (ref "R21") (pin "1") (pinfunction "1_1") (pintype "passive"))
    )
    (net (code "45") (name "Net-(IC2-VO2)") (class "Default")
      (node (ref "IC2") (pin "8") (pinfunction "VO2_8") (pintype "output"))
      (node (ref "SP4") (pin "2") (pinfunction "2_2") (pintype "passive"))
    )
    (net (code "46") (name "Net-(IC4-FC1)") (class "Default")
      (node (ref "C46") (pin "1") (pinfunction "1_1") (pintype "passive"))
      (node (ref "IC4") (pin "3") (pinfunction "FC1_3") (pintype "passive"))
    )
    (net (code "47") (name "Net-(IC4-FC2)") (class "Default")
      (node (ref "C45") (pin "1") (pinfunction "1_1") (pintype "passive"))
      (node (ref "IC4") (pin "2") (pinfunction "FC2_2") (pintype "passive"))
    )
    (net (code "48") (name "Net-(IC4-IN)") (class "Default")
      (node (ref "IC4") (pin "4") (pinfunction "IN_4") (pintype "input"))
      (node (ref "R47") (pin "1") (pinfunction "1_1") (pintype "passive"))
      (node (ref "R48") (pin "2") (pinfunction "2_2") (pintype "passive"))
    )
    (net (code "49") (name "Net-(IC4-VO1)") (class "Default")
      (node (ref "IC4") (pin "5") (pinfunction "VO1_5") (pintype "output"))
      (node (ref "J1") (pin "2") (pinfunction "2_2") (pintype "passive"))
      (node (ref "R48") (pin "1") (pinfunction "1_1") (pintype "passive"))
    )
    (net (code "50") (name "Net-(IC4-VO2)") (class "Default")
      (node (ref "IC4") (pin "8") (pinfunction "VO2_8") (pintype "output"))
      (node (ref "SP2") (pin "2") (pinfunction "2_2") (pintype "passive"))
    )
    (net (code "51") (name "Net-(IC5-1Y)") (class "Default")
      (node (ref "IC5") (pin "3") (pinfunction "1Y_3") (pintype "bidirectional"))
      (node (ref "U$2") (pin "VIN") (pinfunction "DIN_VIN") (pintype "input"))
    )
    (net (code "52") (name "Net-(J1-Pad10)") (class "Default")
      (node (ref "J1") (pin "10") (pinfunction "10_10") (pintype "passive"))
      (node (ref "SP2") (pin "1") (pinfunction "1_1") (pintype "passive"))
    )
    (net (code "53") (name "Net-(J1-Pad11)") (class "Default")
      (node (ref "J1") (pin "11") (pinfunction "11_11") (pintype "passive"))
      (node (ref "SP4") (pin "1") (pinfunction "1_1") (pintype "passive"))
    )
    (net (code "54") (name "Net-(KEYPAD-PadCOL1)") (class "Default")
      (node (ref "KEYPAD") (pin "COL1") (pinfunction "COL1_COL1") (pintype "bidirectional"))
      (node (ref "R43") (pin "1") (pinfunction "1_1") (pintype "passive"))
    )
    (net (code "55") (name "Net-(KEYPAD-PadCOL2)") (class "Default")
      (node (ref "KEYPAD") (pin "COL2") (pinfunction "COL2_COL2") (pintype "bidirectional"))
      (node (ref "R41") (pin "1") (pinfunction "1_1") (pintype "passive"))
    )
    (net (code "56") (name "Net-(KEYPAD-PadCOL3)") (class "Default")
      (node (ref "KEYPAD") (pin "COL3") (pinfunction "COL3_COL3") (pintype "bidirectional"))
      (node (ref "R35") (pin "1") (pinfunction "1_1") (pintype "passive"))
    )
    (net (code "57") (name "Net-(LED1-PadA)") (class "Default")
      (node (ref "LED1") (pin "A") (pinfunction "A_A") (pintype "passive"))
      (node (ref "R1") (pin "1") (pinfunction "1_1") (pintype "passive"))
    )
    (net (code "58") (name "Net-(LED2-PadA)") (class "Default")
      (node (ref "LED2") (pin "A") (pinfunction "A_A") (pintype "passive"))
      (node (ref "R4") (pin "1") (pinfunction "1_1") (pintype "passive"))
    )
    (net (code "59") (name "Net-(RESET-S)") (class "Default")
      (node (ref "C15") (pin "1") (pinfunction "1_1") (pintype "passive"))
      (node (ref "R2") (pin "1") (pinfunction "1_1") (pintype "passive"))
      (node (ref "RESET") (pin "1") (pinfunction "S_1") (pintype "passive"))
      (node (ref "RESET") (pin "2") (pinfunction "S1_2") (pintype "passive"))
      (node (ref "U1") (pin "38") (pinfunction "~{RST}_38") (pintype "bidirectional"))
    )
    (net (code "60") (name "Net-(U$3-CARD_CS)") (class "Default")
      (node (ref "U$3") (pin "5") (pinfunction "CARD_CS_5") (pintype "bidirectional"))
      (node (ref "U1") (pin "18") (pinfunction "PA1_18") (pintype "bidirectional"))
    )
    (net (code "61") (name "Net-(U1G-OSC0)") (class "Default")
      (node (ref "C12") (pin "1") (pinfunction "1_1") (pintype "passive"))
      (node (ref "U1") (pin "40") (pinfunction "OSC0_40") (pintype "bidirectional"))
      (node (ref "Y1") (pin "OSC0") (pinfunction "P$1_OSC0") (pintype "bidirectional"))
    )
    (net (code "62") (name "Net-(U1G-OSC1)") (class "Default")
      (node (ref "C11") (pin "1") (pinfunction "1_1") (pintype "passive"))
      (node (ref "U1") (pin "41") (pinfunction "OSC1_41") (pintype "bidirectional"))
      (node (ref "Y1") (pin "OSC1") (pinfunction "P$2_OSC1") (pintype "bidirectional"))
    )
    (net (code "63") (name "Net-(U1G-~{WAKE})") (class "Default")
      (node (ref "R3") (pin "2") (pinfunction "2_2") (pintype "passive"))
      (node (ref "U1") (pin "32") (pinfunction "~{WAKE}_32") (pintype "bidirectional"))
    )
    (net (code "64") (name "Net-(U2-ADJ_{slash}_GND)") (class "Default")
      (node (ref "C28") (pin "+") (pinfunction "+_+") (pintype "passive"))
      (node (ref "U2") (pin "1") (pinfunction "ADJ_/_GND_1") (pintype "power_in"))
    )
    (net (code "65") (name "Net-(U4-OUTA)") (class "Default")
      (node (ref "C48") (pin "1") (pinfunction "1_1") (pintype "passive"))
      (node (ref "DACOUTA") (pin "P$1") (pinfunction "TP_P$1") (pintype "bidirectional"))
      (node (ref "DACOUTA") (pin "P$2") (pinfunction "TP_P$2") (pintype "bidirectional"))
      (node (ref "U4") (pin "4") (pinfunction "OUTA_4") (pintype "output"))
    )
    (net (code "66") (name "Net-(U4-OUTB)") (class "Default")
      (node (ref "C44") (pin "2") (pinfunction "2_2") (pintype "passive"))
      (node (ref "DACOUTB") (pin "P$1") (pinfunction "TP_P$1") (pintype "bidirectional"))
      (node (ref "DACOUTB") (pin "P$2") (pinfunction "TP_P$2") (pintype "bidirectional"))
      (node (ref "U4") (pin "7") (pinfunction "OUTB_7") (pintype "output"))
    )
    (net (code "67") (name "unconnected-(IC2-CD-Pad1)") (class "Default")
      (node (ref "IC2") (pin "1") (pinfunction "CD_1") (pintype "passive"))
    )
    (net (code "68") (name "unconnected-(IC4-CD-Pad1)") (class "Default")
      (node (ref "IC4") (pin "1") (pinfunction "CD_1") (pintype "passive"))
    )
    (net (code "69") (name "unconnected-(IC5-2A-Pad5)") (class "Default")
      (node (ref "IC5") (pin "5") (pinfunction "2A_5") (pintype "bidirectional"))
    )
    (net (code "70") (name "unconnected-(IC5-2OE-Pad4)") (class "Default")
      (node (ref "IC5") (pin "4") (pinfunction "2OE_4") (pintype "bidirectional"))
    )
    (net (code "71") (name "unconnected-(IC5-2Y-Pad6)") (class "Default")
      (node (ref "IC5") (pin "6") (pinfunction "2Y_6") (pintype "bidirectional"))
    )
    (net (code "72") (name "unconnected-(IC5-3A-Pad9)") (class "Default")
      (node (ref "IC5") (pin "9") (pinfunction "3A_9") (pintype "bidirectional"))
    )
    (net (code "73") (name "unconnected-(IC5-3OE-Pad10)") (class "Default")
      (node (ref "IC5") (pin "10") (pinfunction "3OE_10") (pintype "bidirectional"))
    )
    (net (code "74") (name "unconnected-(IC5-3Y-Pad8)") (class "Default")
      (node (ref "IC5") (pin "8") (pinfunction "3Y_8") (pintype "bidirectional"))
    )
    (net (code "75") (name "unconnected-(IC5-4A-Pad12)") (class "Default")
      (node (ref "IC5") (pin "12") (pinfunction "4A_12") (pintype "bidirectional"))
    )
    (net (code "76") (name "unconnected-(IC5-4OE-Pad13)") (class "Default")
      (node (ref "IC5") (pin "13") (pinfunction "4OE_13") (pintype "bidirectional"))
    )
    (net (code "77") (name "unconnected-(IC5-4Y-Pad11)") (class "Default")
      (node (ref "IC5") (pin "11") (pinfunction "4Y_11") (pintype "bidirectional"))
    )
    (net (code "78") (name "unconnected-(S1-Pad1)") (class "Default")
      (node (ref "S1") (pin "1") (pinfunction "1_1") (pintype "passive"))
    )
    (net (code "79") (name "unconnected-(U1A-PA0-Pad17)") (class "Default")
      (node (ref "U1") (pin "17") (pinfunction "PA0_17") (pintype "bidirectional"))
    )
    (net (code "80") (name "unconnected-(U1B-PB7-Pad4)") (class "Default")
      (node (ref "U1") (pin "4") (pinfunction "PB7_4") (pintype "bidirectional"))
    )
    (net (code "81") (name "unconnected-(U1C-PC4-Pad16)") (class "Default")
      (node (ref "U1") (pin "16") (pinfunction "PC4_16") (pintype "bidirectional"))
    )
    (net (code "82") (name "unconnected-(U1C-PC5-Pad15)") (class "Default")
      (node (ref "U1") (pin "15") (pinfunction "PC5_15") (pintype "bidirectional"))
    )
    (net (code "83") (name "unconnected-(U1C-PC6-Pad14)") (class "Default")
      (node (ref "U1") (pin "14") (pinfunction "PC6_14") (pintype "bidirectional"))
    )
    (net (code "84") (name "unconnected-(U1C-PC7-Pad13)") (class "Default")
      (node (ref "U1") (pin "13") (pinfunction "PC7_13") (pintype "bidirectional"))
    )
    (net (code "85") (name "unconnected-(U1D-PD2-Pad63)") (class "Default")
      (node (ref "U1") (pin "63") (pinfunction "PD2_63") (pintype "bidirectional"))
    )
    (net (code "86") (name "unconnected-(U1E-PE4-Pad59)") (class "Default")
      (node (ref "U1") (pin "59") (pinfunction "PE4_59") (pintype "bidirectional"))
    )
    (net (code "87") (name "unconnected-(U1E-PE5-Pad60)") (class "Default")
      (node (ref "U1") (pin "60") (pinfunction "PE5_60") (pintype "bidirectional"))
    )
    (net (code "88") (name "unconnected-(U1G-XOSC1-Pad36)") (class "Default")
      (node (ref "U1") (pin "36") (pinfunction "XOSC1_36") (pintype "bidirectional"))
    )
    (net (code "89") (name "unconnected-(U1G-~{HIB}-Pad33)") (class "Default")
      (node (ref "U1") (pin "33") (pinfunction "~{HIB}_33") (pintype "bidirectional"))
    )
  )
)
